# bonnie.net
KiCad netlist of a schematic drawn in EAGLE
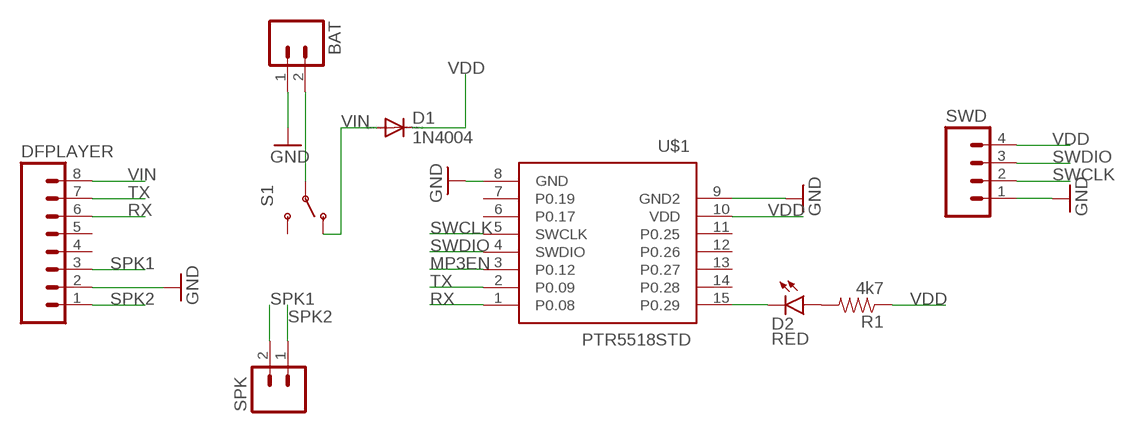
[diagram p0: schematic, sheet 1]

(export (version "E")
  (design (tool "Eeschema 10.0.6"))
  (components
    (comp (ref "BAT")
      (value "M02JST-PTH-2")
      (footprint "eagle-import:JST-2-PTH")
      (libsource (lib "eagle-import") (part "M02JST-PTH-2"))
    )
    (comp (ref "D1")
      (value "1N4004")
      (footprint "eagle-import:DO41-10")
      (libsource (lib "eagle-import") (part "1N4004"))
    )
    (comp (ref "D2")
      (value "RED")
      (footprint "eagle-import:LED-1206")
      (libsource (lib "eagle-import") (part "LED-RED1206"))
    )
    (comp (ref "DFPLAYER")
      (value "M08LOCK")
      (footprint "eagle-import:1X08_LOCK")
      (libsource (lib "eagle-import") (part "M08LOCK"))
    )
    (comp (ref "R1")
      (value "4k7")
      (footprint "eagle-import:0603-RES")
      (libsource (lib "eagle-import") (part "4.7OHM-1/10W-5%(0603)"))
    )
    (comp (ref "S1")
      (value "SWITCH-SPDTPTH")
      (footprint "eagle-import:SWITCH-SPDT")
      (libsource (lib "eagle-import") (part "SWITCH-SPDTPTH"))
    )
    (comp (ref "SPK")
      (value "M02JST-PTH-2")
      (footprint "eagle-import:JST-2-PTH")
      (libsource (lib "eagle-import") (part "M02JST-PTH-2"))
    )
    (comp (ref "SWD")
      (value "M04LOCK")
      (footprint "eagle-import:1X04_LOCK")
      (libsource (lib "eagle-import") (part "M04LOCK"))
    )
    (comp (ref "U$1")
      (value "PTR5518STD")
      (footprint "eagle-import:PTR5518")
      (libsource (lib "eagle-import") (part "PTR5518STD"))
    )
  )
  (nets
    (net (code "1") (name "/MP3EN") (class "Default")
      (node (ref "U$1") (pin "3") (pinfunction "P0.12_3") (pintype "bidirectional"))
    )
    (net (code "2") (name "/RX") (class "Default")
      (node (ref "DFPLAYER") (pin "6") (pinfunction "6_6") (pintype "passive"))
      (node (ref "U$1") (pin "1") (pinfunction "P0.08_1") (pintype "bidirectional"))
    )
    (net (code "3") (name "/SPK1") (class "Default")
      (node (ref "DFPLAYER") (pin "3") (pinfunction "3_3") (pintype "passive"))
      (node (ref "SPK") (pin "2") (pinfunction "2_2") (pintype "passive"))
    )
    (net (code "4") (name "/SPK2") (class "Default")
      (node (ref "DFPLAYER") (pin "1") (pinfunction "1_1") (pintype "passive"))
      (node (ref "SPK") (pin "1") (pinfunction "1_1") (pintype "passive"))
    )
    (net (code "5") (name "/SWCLK") (class "Default")
      (node (ref "SWD") (pin "2") (pinfunction "2_2") (pintype "passive"))
      (node (ref "U$1") (pin "5") (pinfunction "SWCLK_5") (pintype "bidirectional"))
    )
    (net (code "6") (name "/SWDIO") (class "Default")
      (node (ref "SWD") (pin "3") (pinfunction "3_3") (pintype "passive"))
      (node (ref "U$1") (pin "4") (pinfunction "SWDIO_4") (pintype "bidirectional"))
    )
    (net (code "7") (name "/TX") (class "Default")
      (node (ref "DFPLAYER") (pin "7") (pinfunction "7_7") (pintype "passive"))
      (node (ref "U$1") (pin "2") (pinfunction "P0.09_2") (pintype "bidirectional"))
    )
    (net (code "8") (name "/VDD") (class "Default")
      (node (ref "D1") (pin "C") (pinfunction "C_C") (pintype "passive"))
      (node (ref "R1") (pin "1") (pinfunction "1_1") (pintype "passive"))
      (node (ref "SWD") (pin "4") (pinfunction "4_4") (pintype "passive"))
      (node (ref "U$1") (pin "10") (pinfunction "VDD_10") (pintype "power_in"))
    )
    (net (code "9") (name "/VIN") (class "Default")
      (node (ref "D1") (pin "A") (pinfunction "A_A") (pintype "passive"))
      (node (ref "DFPLAYER") (pin "8") (pinfunction "8_8") (pintype "passive"))
      (node (ref "S1") (pin "1") (pinfunction "O_1") (pintype "passive"))
    )
    (net (code "10") (name "GND") (class "Default")
      (node (ref "BAT") (pin "1") (pinfunction "1_1") (pintype "passive"))
      (node (ref "DFPLAYER") (pin "2") (pinfunction "2_2") (pintype "passive"))
      (node (ref "SWD") (pin "1") (pinfunction "1_1") (pintype "passive"))
      (node (ref "U$1") (pin "8") (pinfunction "GND_8") (pintype "power_in"))
      (node (ref "U$1") (pin "9") (pinfunction "GND2_9") (pintype "power_in"))
    )
    (net (code "11") (name "Net-(D2-PadA)") (class "Default")
      (node (ref "D2") (pin "A") (pinfunction "A_A") (pintype "passive"))
      (node (ref "R1") (pin "2") (pinfunction "2_2") (pintype "passive"))
    )
    (net (code "12") (name "Net-(S1-P)") (class "Default")
      (node (ref "BAT") (pin "2") (pinfunction "2_2") (pintype "passive"))
      (node (ref "S1") (pin "2") (pinfunction "P_2") (pintype "passive"))
    )
    (net (code "13") (name "Net-(U$1-P0.29)") (class "Default")
      (node (ref "D2") (pin "C") (pinfunction "C_C") (pintype "passive"))
      (node (ref "U$1") (pin "15") (pinfunction "P0.29_15") (pintype "bidirectional"))
    )
    (net (code "14") (name "unconnected-(DFPLAYER-Pad4)") (class "Default")
      (node (ref "DFPLAYER") (pin "4") (pinfunction "4_4") (pintype "passive"))
    )
    (net (code "15") (name "unconnected-(DFPLAYER-Pad5)") (class "Default")
      (node (ref "DFPLAYER") (pin "5") (pinfunction "5_5") (pintype "passive"))
    )
    (net (code "16") (name "unconnected-(S1-S-Pad3)") (class "Default")
      (node (ref "S1") (pin "3") (pinfunction "S_3") (pintype "passive"))
    )
    (net (code "17") (name "unconnected-(U$1-P0.17-Pad6)") (class "Default")
      (node (ref "U$1") (pin "6") (pinfunction "P0.17_6") (pintype "bidirectional"))
    )
    (net (code "18") (name "unconnected-(U$1-P0.19-Pad7)") (class "Default")
      (node (ref "U$1") (pin "7") (pinfunction "P0.19_7") (pintype "bidirectional"))
    )
    (net (code "19") (name "unconnected-(U$1-P0.25-Pad11)") (class "Default")
      (node (ref "U$1") (pin "11") (pinfunction "P0.25_11") (pintype "bidirectional"))
    )
    (net (code "20") (name "unconnected-(U$1-P0.26-Pad12)") (class "Default")
      (node (ref "U$1") (pin "12") (pinfunction "P0.26_12") (pintype "bidirectional"))
    )
    (net (code "21") (name "unconnected-(U$1-P0.27-Pad13)") (class "Default")
      (node (ref "U$1") (pin "13") (pinfunction "P0.27_13") (pintype "bidirectional"))
    )
    (net (code "22") (name "unconnected-(U$1-P0.28-Pad14)") (class "Default")
      (node (ref "U$1") (pin "14") (pinfunction "P0.28_14") (pintype "bidirectional"))
    )
  )
)
